# Audio.net
KiCad netlist of a schematic drawn in Altium Designer
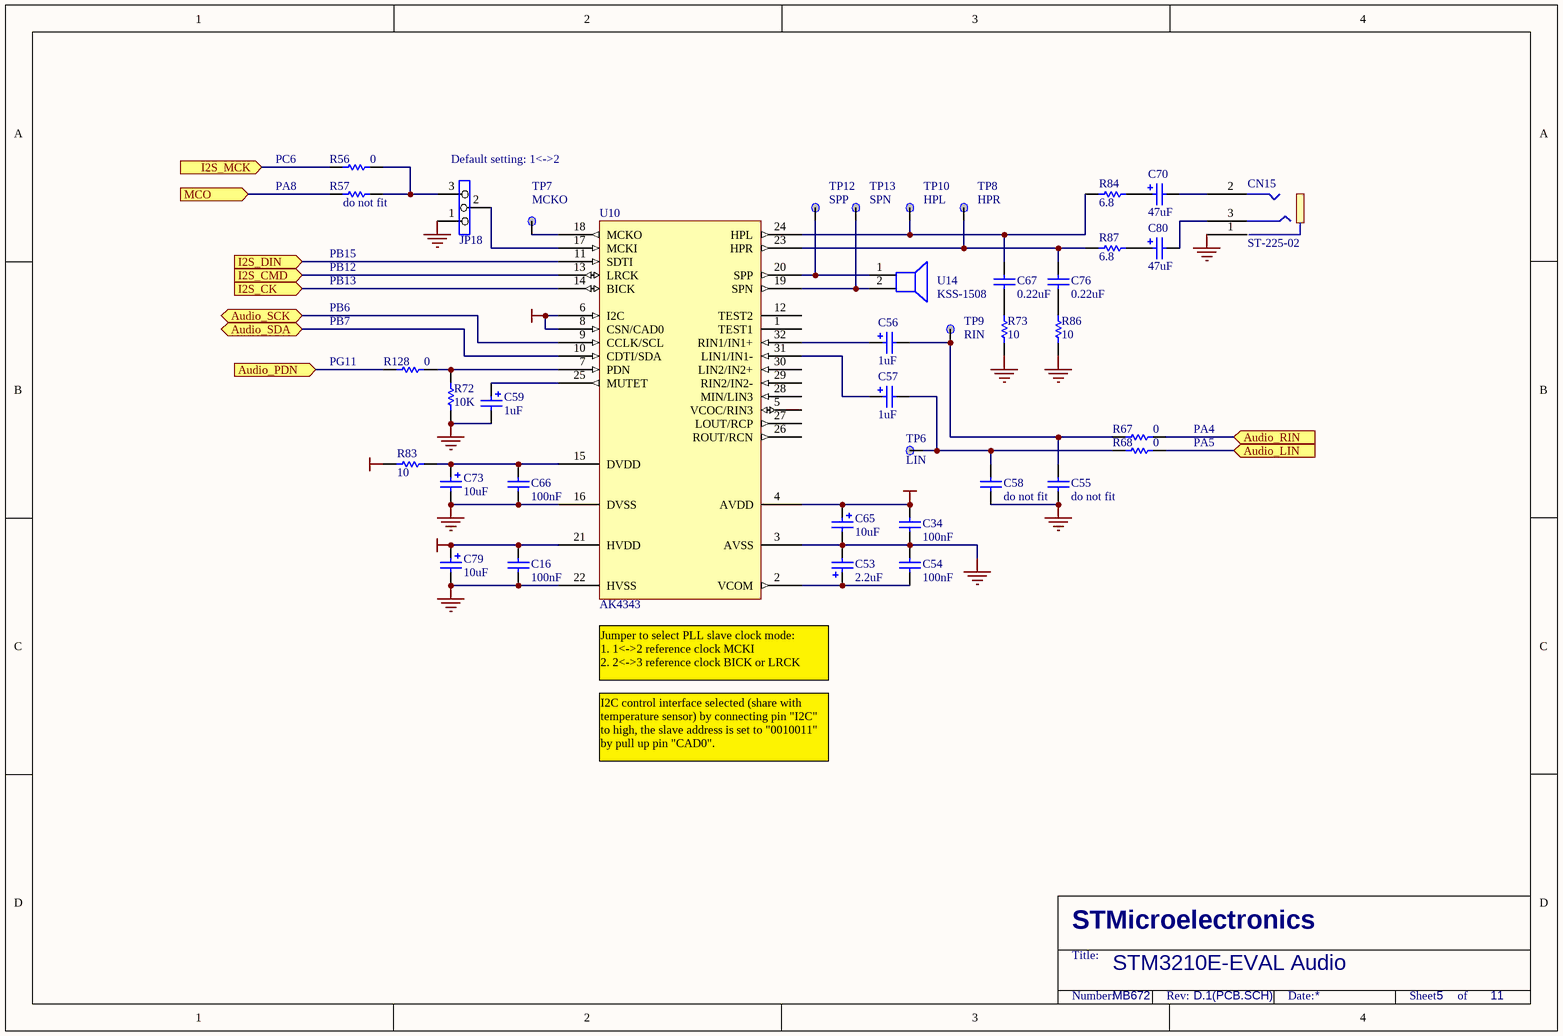
[diagram p0: Audio.SchDoc]

(export (version "E")
  (design (tool "Eeschema 10.0.6"))
  (components
    (comp (ref "C16")
      (value "100nF")
      (footprint "0603P")
      (description "Capacitor")
      (fields (field (name "PUBLISHER") "Altium Limited"))
      (libsource (lib "Miscellaneous Devices") (part "CAP"))
    )
    (comp (ref "C34")
      (value "100nF")
      (footprint "0603P")
      (description "Capacitor")
      (fields (field (name "PUBLISHER") "Altium Limited"))
      (libsource (lib "Miscellaneous Devices") (part "CAP"))
    )
    (comp (ref "C53")
      (value "2.2uF")
      (footprint "C160M")
      (description "Polarized Capacitor (Radial)")
      (fields (field (name "PUBLISHER") "Altium Limited"))
      (libsource (lib "Miscellaneous Devices") (part "Cap Pol1"))
    )
    (comp (ref "C54")
      (value "100nF")
      (footprint "0603P")
      (description "Capacitor")
      (fields (field (name "PUBLISHER") "Altium Limited"))
      (libsource (lib "Miscellaneous Devices") (part "CAP"))
    )
    (comp (ref "C55")
      (value "do not fit")
      (footprint "0603P")
      (description "Capacitor")
      (fields (field (name "PUBLISHER") "Altium Limited"))
      (libsource (lib "Miscellaneous Devices") (part "CAP"))
    )
    (comp (ref "C56")
      (value "1uF")
      (footprint "C160M")
      (description "Polarized Capacitor (Radial)")
      (fields (field (name "PUBLISHER") "Altium Limited"))
      (libsource (lib "Miscellaneous Devices") (part "Cap Pol1"))
    )
    (comp (ref "C57")
      (value "1uF")
      (footprint "C160M")
      (description "Polarized Capacitor (Radial)")
      (fields (field (name "PUBLISHER") "Altium Limited"))
      (libsource (lib "Miscellaneous Devices") (part "Cap Pol1"))
    )
    (comp (ref "C58")
      (value "do not fit")
      (footprint "0603P")
      (description "Capacitor")
      (fields (field (name "PUBLISHER") "Altium Limited"))
      (libsource (lib "Miscellaneous Devices") (part "CAP"))
    )
    (comp (ref "C59")
      (value "1uF")
      (footprint "C160M")
      (description "Polarized Capacitor (Radial)")
      (fields (field (name "PUBLISHER") "Altium Limited"))
      (libsource (lib "Miscellaneous Devices") (part "Cap Pol1"))
    )
    (comp (ref "C65")
      (value "10uF")
      (footprint "C160M")
      (description "Polarized Capacitor (Radial)")
      (fields (field (name "PUBLISHER") "Altium Limited"))
      (libsource (lib "Miscellaneous Devices") (part "Cap Pol1"))
    )
    (comp (ref "C66")
      (value "100nF")
      (footprint "0603P")
      (description "Capacitor")
      (fields (field (name "PUBLISHER") "Altium Limited"))
      (libsource (lib "Miscellaneous Devices") (part "CAP"))
    )
    (comp (ref "C67")
      (value "0.22uF")
      (footprint "0603P")
      (description "Capacitor")
      (fields (field (name "PUBLISHER") "Altium Limited"))
      (libsource (lib "Miscellaneous Devices") (part "CAP"))
    )
    (comp (ref "C70")
      (value "47uF")
      (footprint "C160M")
      (description "Polarized Capacitor (Radial)")
      (fields (field (name "PUBLISHER") "Altium Limited"))
      (libsource (lib "Miscellaneous Devices") (part "Cap Pol1"))
    )
    (comp (ref "C73")
      (value "10uF")
      (footprint "C160M")
      (description "Polarized Capacitor (Radial)")
      (fields (field (name "PUBLISHER") "Altium Limited"))
      (libsource (lib "Miscellaneous Devices") (part "Cap Pol1"))
    )
    (comp (ref "C76")
      (value "0.22uF")
      (footprint "0603P")
      (description "Capacitor")
      (fields (field (name "PUBLISHER") "Altium Limited"))
      (libsource (lib "Miscellaneous Devices") (part "CAP"))
    )
    (comp (ref "C79")
      (value "10uF")
      (footprint "C160M")
      (description "Polarized Capacitor (Radial)")
      (fields (field (name "PUBLISHER") "Altium Limited"))
      (libsource (lib "Miscellaneous Devices") (part "Cap Pol1"))
    )
    (comp (ref "C80")
      (value "47uF")
      (footprint "C160M")
      (description "Polarized Capacitor (Radial)")
      (fields (field (name "PUBLISHER") "Altium Limited"))
      (libsource (lib "Miscellaneous Devices") (part "Cap Pol1"))
    )
    (comp (ref "CN15") (value "ST-225-02") (libsource (lib "MB672") (part "ST-225-02")))
    (comp (ref "JP18") (value "~") (footprint "SIP3") (libsource (lib "STR910_SCHLIB") (part "Jumper3")))
    (comp (ref "R56")
      (value "0")
      (description "Resistor")
      (fields (field (name "PUBLISHER") "Altium Limited"))
      (libsource (lib "Miscellaneous Devices") (part "res1"))
    )
    (comp (ref "R57")
      (value "do not fit")
      (description "Resistor")
      (fields (field (name "PUBLISHER") "Altium Limited"))
      (libsource (lib "Miscellaneous Devices") (part "res1"))
    )
    (comp (ref "R67")
      (value "0")
      (description "Resistor")
      (fields (field (name "PUBLISHER") "Altium Limited"))
      (libsource (lib "Miscellaneous Devices") (part "res1"))
    )
    (comp (ref "R68")
      (value "0")
      (description "Resistor")
      (fields (field (name "PUBLISHER") "Altium Limited"))
      (libsource (lib "Miscellaneous Devices") (part "res1"))
    )
    (comp (ref "R72")
      (value "10K")
      (description "Resistor")
      (fields (field (name "PUBLISHER") "Altium Limited"))
      (libsource (lib "Miscellaneous Devices") (part "res1"))
    )
    (comp (ref "R73")
      (value "10")
      (description "Resistor")
      (fields (field (name "PUBLISHER") "Altium Limited"))
      (libsource (lib "Miscellaneous Devices") (part "res1"))
    )
    (comp (ref "R83")
      (value "10")
      (description "Resistor")
      (fields (field (name "PUBLISHER") "Altium Limited"))
      (libsource (lib "Miscellaneous Devices") (part "res1"))
    )
    (comp (ref "R84")
      (value "6.8")
      (description "Resistor")
      (fields (field (name "PUBLISHER") "Altium Limited"))
      (libsource (lib "Miscellaneous Devices") (part "res1"))
    )
    (comp (ref "R86")
      (value "10")
      (description "Resistor")
      (fields (field (name "PUBLISHER") "Altium Limited"))
      (libsource (lib "Miscellaneous Devices") (part "res1"))
    )
    (comp (ref "R87")
      (value "6.8")
      (description "Resistor")
      (fields (field (name "PUBLISHER") "Altium Limited"))
      (libsource (lib "Miscellaneous Devices") (part "res1"))
    )
    (comp (ref "R128")
      (value "0")
      (description "Resistor")
      (fields (field (name "PUBLISHER") "Altium Limited"))
      (libsource (lib "Miscellaneous Devices") (part "res1"))
    )
    (comp (ref "TP6") (value "LIN") (footprint "TP") (libsource (lib "*") (part "TP")))
    (comp (ref "TP7") (value "MCKO") (footprint "TP") (libsource (lib "*") (part "TP")))
    (comp (ref "TP8") (value "HPR") (footprint "TP") (libsource (lib "*") (part "TP")))
    (comp (ref "TP9") (value "RIN") (footprint "TP") (libsource (lib "*") (part "TP")))
    (comp (ref "TP10") (value "HPL") (footprint "TP") (libsource (lib "*") (part "TP")))
    (comp (ref "TP12") (value "SPP") (footprint "TP") (libsource (lib "*") (part "TP")))
    (comp (ref "TP13") (value "SPN") (footprint "TP") (libsource (lib "*") (part "TP")))
    (comp (ref "U10") (value "AK4343") (footprint "QFN32") (libsource (lib "MB672") (part "AK4343")))
    (comp (ref "U14")
      (value "KSS-1508")
      (footprint "KS1508")
      (description "Loudspeaker")
      (fields (field (name "PUBLISHER") "Altium Limited"))
      (libsource (lib "Miscellaneous Devices") (part "Speaker"))
    )
  )
  (nets
    (net (code "1") (name "+3V3") (class "Default")
      (node (ref "C16") (pin "1") (pinfunction "1_1") (pintype "passive"))
      (node (ref "C34") (pin "2") (pinfunction "2_2") (pintype "passive"))
      (node (ref "C65") (pin "1") (pinfunction "1_1") (pintype "passive"))
      (node (ref "C79") (pin "1") (pinfunction "1_1") (pintype "passive"))
      (node (ref "R83") (pin "2") (pinfunction "2_2") (pintype "passive"))
      (node (ref "U10") (pin "21") (pinfunction "HVDD_21") (pintype "passive"))
      (node (ref "U10") (pin "4") (pinfunction "AVDD_4") (pintype "passive"))
      (node (ref "U10") (pin "6") (pinfunction "I2C_6") (pintype "input"))
      (node (ref "U10") (pin "8") (pinfunction "CSN/CAD0_8") (pintype "input"))
    )
    (net (code "2") (name "/Audio_LIN") (class "Default")
      (node (ref "R68") (pin "2") (pinfunction "2_2") (pintype "passive"))
    )
    (net (code "3") (name "/Audio_PDN") (class "Default")
      (node (ref "R128") (pin "2") (pinfunction "2_2") (pintype "passive"))
    )
    (net (code "4") (name "/Audio_RIN") (class "Default")
      (node (ref "R67") (pin "2") (pinfunction "2_2") (pintype "passive"))
    )
    (net (code "5") (name "/Audio_SCK") (class "Default")
      (node (ref "U10") (pin "9") (pinfunction "CCLK/SCL_9") (pintype "input"))
    )
    (net (code "6") (name "/Audio_SDA") (class "Default")
      (node (ref "U10") (pin "10") (pinfunction "CDTI/SDA_10") (pintype "input"))
    )
    (net (code "7") (name "/I2S_CK") (class "Default")
      (node (ref "U10") (pin "14") (pinfunction "BICK_14") (pintype "bidirectional"))
    )
    (net (code "8") (name "/I2S_CMD") (class "Default")
      (node (ref "U10") (pin "13") (pinfunction "LRCK_13") (pintype "bidirectional"))
    )
    (net (code "9") (name "/I2S_DIN") (class "Default")
      (node (ref "U10") (pin "11") (pinfunction "SDTI_11") (pintype "input"))
    )
    (net (code "10") (name "/I2S_MCK") (class "Default")
      (node (ref "R56") (pin "2") (pinfunction "2_2") (pintype "passive"))
    )
    (net (code "11") (name "/MCO") (class "Default")
      (node (ref "R57") (pin "2") (pinfunction "2_2") (pintype "passive"))
    )
    (net (code "12") (name "GND") (class "Default")
      (node (ref "C16") (pin "2") (pinfunction "2_2") (pintype "passive"))
      (node (ref "C34") (pin "1") (pinfunction "1_1") (pintype "passive"))
      (node (ref "C53") (pin "2") (pinfunction "2_2") (pintype "passive"))
      (node (ref "C54") (pin "2") (pinfunction "2_2") (pintype "passive"))
      (node (ref "C55") (pin "1") (pinfunction "1_1") (pintype "passive"))
      (node (ref "C58") (pin "1") (pinfunction "1_1") (pintype "passive"))
      (node (ref "C59") (pin "2") (pinfunction "2_2") (pintype "passive"))
      (node (ref "C65") (pin "2") (pinfunction "2_2") (pintype "passive"))
      (node (ref "C66") (pin "2") (pinfunction "2_2") (pintype "passive"))
      (node (ref "C73") (pin "2") (pinfunction "2_2") (pintype "passive"))
      (node (ref "C79") (pin "2") (pinfunction "2_2") (pintype "passive"))
      (node (ref "CN15") (pin "1") (pintype "passive"))
      (node (ref "JP18") (pin "1") (pintype "passive"))
      (node (ref "R72") (pin "2") (pinfunction "2_2") (pintype "passive"))
      (node (ref "R73") (pin "2") (pinfunction "2_2") (pintype "passive"))
      (node (ref "R86") (pin "2") (pinfunction "2_2") (pintype "passive"))
      (node (ref "U10") (pin "16") (pinfunction "DVSS_16") (pintype "passive"))
      (node (ref "U10") (pin "22") (pinfunction "HVSS_22") (pintype "passive"))
      (node (ref "U10") (pin "3") (pinfunction "AVSS_3") (pintype "passive"))
    )
    (net (code "13") (name "Net-(C55-Pad2)") (class "Default")
      (node (ref "C55") (pin "2") (pinfunction "2_2") (pintype "passive"))
      (node (ref "C56") (pin "2") (pinfunction "2_2") (pintype "passive"))
      (node (ref "R67") (pin "1") (pinfunction "1_1") (pintype "passive"))
      (node (ref "TP9") (pin "1") (pinfunction "1_1") (pintype "passive"))
    )
    (net (code "14") (name "Net-(C57-Pad2)") (class "Default")
      (node (ref "C57") (pin "2") (pinfunction "2_2") (pintype "passive"))
      (node (ref "C58") (pin "2") (pinfunction "2_2") (pintype "passive"))
      (node (ref "R68") (pin "1") (pinfunction "1_1") (pintype "passive"))
      (node (ref "TP6") (pin "1") (pinfunction "1_1") (pintype "passive"))
    )
    (net (code "15") (name "Net-(C67-Pad2)") (class "Default")
      (node (ref "C67") (pin "2") (pinfunction "2_2") (pintype "passive"))
      (node (ref "R73") (pin "1") (pinfunction "1_1") (pintype "passive"))
    )
    (net (code "16") (name "Net-(C70-Pad1)") (class "Default")
      (node (ref "C70") (pin "1") (pinfunction "1_1") (pintype "passive"))
      (node (ref "R84") (pin "1") (pinfunction "1_1") (pintype "passive"))
    )
    (net (code "17") (name "Net-(C70-Pad2)") (class "Default")
      (node (ref "C70") (pin "2") (pinfunction "2_2") (pintype "passive"))
      (node (ref "CN15") (pin "2") (pintype "passive"))
    )
    (net (code "18") (name "Net-(C76-Pad2)") (class "Default")
      (node (ref "C76") (pin "2") (pinfunction "2_2") (pintype "passive"))
      (node (ref "R86") (pin "1") (pinfunction "1_1") (pintype "passive"))
    )
    (net (code "19") (name "Net-(C80-Pad1)") (class "Default")
      (node (ref "C80") (pin "1") (pinfunction "1_1") (pintype "passive"))
      (node (ref "R87") (pin "1") (pinfunction "1_1") (pintype "passive"))
    )
    (net (code "20") (name "Net-(C80-Pad2)") (class "Default")
      (node (ref "C80") (pin "2") (pinfunction "2_2") (pintype "passive"))
      (node (ref "CN15") (pin "3") (pintype "passive"))
    )
    (net (code "21") (name "Net-(JP18-Pad3)") (class "Default")
      (node (ref "JP18") (pin "3") (pintype "passive"))
      (node (ref "R56") (pin "1") (pinfunction "1_1") (pintype "passive"))
      (node (ref "R57") (pin "1") (pinfunction "1_1") (pintype "passive"))
    )
    (net (code "22") (name "Net-(U10-DVDD)") (class "Default")
      (node (ref "C66") (pin "1") (pinfunction "1_1") (pintype "passive"))
      (node (ref "C73") (pin "1") (pinfunction "1_1") (pintype "passive"))
      (node (ref "R83") (pin "1") (pinfunction "1_1") (pintype "passive"))
      (node (ref "U10") (pin "15") (pinfunction "DVDD_15") (pintype "passive"))
    )
    (net (code "23") (name "Net-(U10-HPL)") (class "Default")
      (node (ref "C67") (pin "1") (pinfunction "1_1") (pintype "passive"))
      (node (ref "R84") (pin "2") (pinfunction "2_2") (pintype "passive"))
      (node (ref "TP10") (pin "1") (pinfunction "1_1") (pintype "passive"))
      (node (ref "U10") (pin "24") (pinfunction "HPL_24") (pintype "output"))
    )
    (net (code "24") (name "Net-(U10-HPR)") (class "Default")
      (node (ref "C76") (pin "1") (pinfunction "1_1") (pintype "passive"))
      (node (ref "R87") (pin "2") (pinfunction "2_2") (pintype "passive"))
      (node (ref "TP8") (pin "1") (pinfunction "1_1") (pintype "passive"))
      (node (ref "U10") (pin "23") (pinfunction "HPR_23") (pintype "output"))
    )
    (net (code "25") (name "Net-(U10-LIN1{slash}IN1-)") (class "Default")
      (node (ref "C57") (pin "1") (pinfunction "1_1") (pintype "passive"))
      (node (ref "U10") (pin "31") (pinfunction "LIN1/IN1-_31") (pintype "input"))
    )
    (net (code "26") (name "Net-(U10-MCKI)") (class "Default")
      (node (ref "JP18") (pin "2") (pintype "passive"))
      (node (ref "U10") (pin "17") (pinfunction "MCKI_17") (pintype "input"))
    )
    (net (code "27") (name "Net-(U10-MCKO)") (class "Default")
      (node (ref "TP7") (pin "1") (pinfunction "1_1") (pintype "passive"))
      (node (ref "U10") (pin "18") (pinfunction "MCKO_18") (pintype "output"))
    )
    (net (code "28") (name "Net-(U10-MUTET)") (class "Default")
      (node (ref "C59") (pin "1") (pinfunction "1_1") (pintype "passive"))
      (node (ref "U10") (pin "25") (pinfunction "MUTET_25") (pintype "output"))
    )
    (net (code "29") (name "Net-(U10-PDN)") (class "Default")
      (node (ref "R128") (pin "1") (pinfunction "1_1") (pintype "passive"))
      (node (ref "R72") (pin "1") (pinfunction "1_1") (pintype "passive"))
      (node (ref "U10") (pin "7") (pinfunction "PDN_7") (pintype "input"))
    )
    (net (code "30") (name "Net-(U10-RIN1{slash}IN1+)") (class "Default")
      (node (ref "C56") (pin "1") (pinfunction "1_1") (pintype "passive"))
      (node (ref "U10") (pin "32") (pinfunction "RIN1/IN1+_32") (pintype "input"))
    )
    (net (code "31") (name "Net-(U10-SPN)") (class "Default")
      (node (ref "TP13") (pin "1") (pinfunction "1_1") (pintype "passive"))
      (node (ref "U10") (pin "19") (pinfunction "SPN_19") (pintype "output"))
      (node (ref "U14") (pin "2") (pinfunction "-_2") (pintype "passive"))
    )
    (net (code "32") (name "Net-(U10-SPP)") (class "Default")
      (node (ref "TP12") (pin "1") (pinfunction "1_1") (pintype "passive"))
      (node (ref "U10") (pin "20") (pinfunction "SPP_20") (pintype "output"))
      (node (ref "U14") (pin "1") (pinfunction "+_1") (pintype "passive"))
    )
    (net (code "33") (name "Net-(U10-VCOM)") (class "Default")
      (node (ref "C53") (pin "1") (pinfunction "1_1") (pintype "passive"))
      (node (ref "C54") (pin "1") (pinfunction "1_1") (pintype "passive"))
      (node (ref "U10") (pin "2") (pinfunction "VCOM_2") (pintype "output"))
    )
    (net (code "34") (name "unconnected-(U10-LIN2{slash}IN2+-Pad30)") (class "Default")
      (node (ref "U10") (pin "30") (pinfunction "LIN2/IN2+_30") (pintype "input"))
    )
    (net (code "35") (name "unconnected-(U10-LOUT{slash}RCP-Pad27)") (class "Default")
      (node (ref "U10") (pin "27") (pinfunction "LOUT/RCP_27") (pintype "output"))
    )
    (net (code "36") (name "unconnected-(U10-MIN{slash}LIN3-Pad28)") (class "Default")
      (node (ref "U10") (pin "28") (pinfunction "MIN/LIN3_28") (pintype "input"))
    )
    (net (code "37") (name "unconnected-(U10-RIN2{slash}IN2--Pad29)") (class "Default")
      (node (ref "U10") (pin "29") (pinfunction "RIN2/IN2-_29") (pintype "input"))
    )
    (net (code "38") (name "unconnected-(U10-ROUT{slash}RCN-Pad26)") (class "Default")
      (node (ref "U10") (pin "26") (pinfunction "ROUT/RCN_26") (pintype "output"))
    )
    (net (code "39") (name "unconnected-(U10-TEST1-Pad1)") (class "Default")
      (node (ref "U10") (pin "1") (pinfunction "TEST1_1") (pintype "passive"))
    )
    (net (code "40") (name "unconnected-(U10-TEST2-Pad12)") (class "Default")
      (node (ref "U10") (pin "12") (pinfunction "TEST2_12") (pintype "passive"))
    )
    (net (code "41") (name "unconnected-(U10-VCOC{slash}RIN3-Pad5)") (class "Default")
      (node (ref "U10") (pin "5") (pinfunction "VCOC/RIN3_5") (pintype "bidirectional"))
    )
  )
)
